# spachausgabe.net
KiCad netlist of a schematic drawn in EAGLE
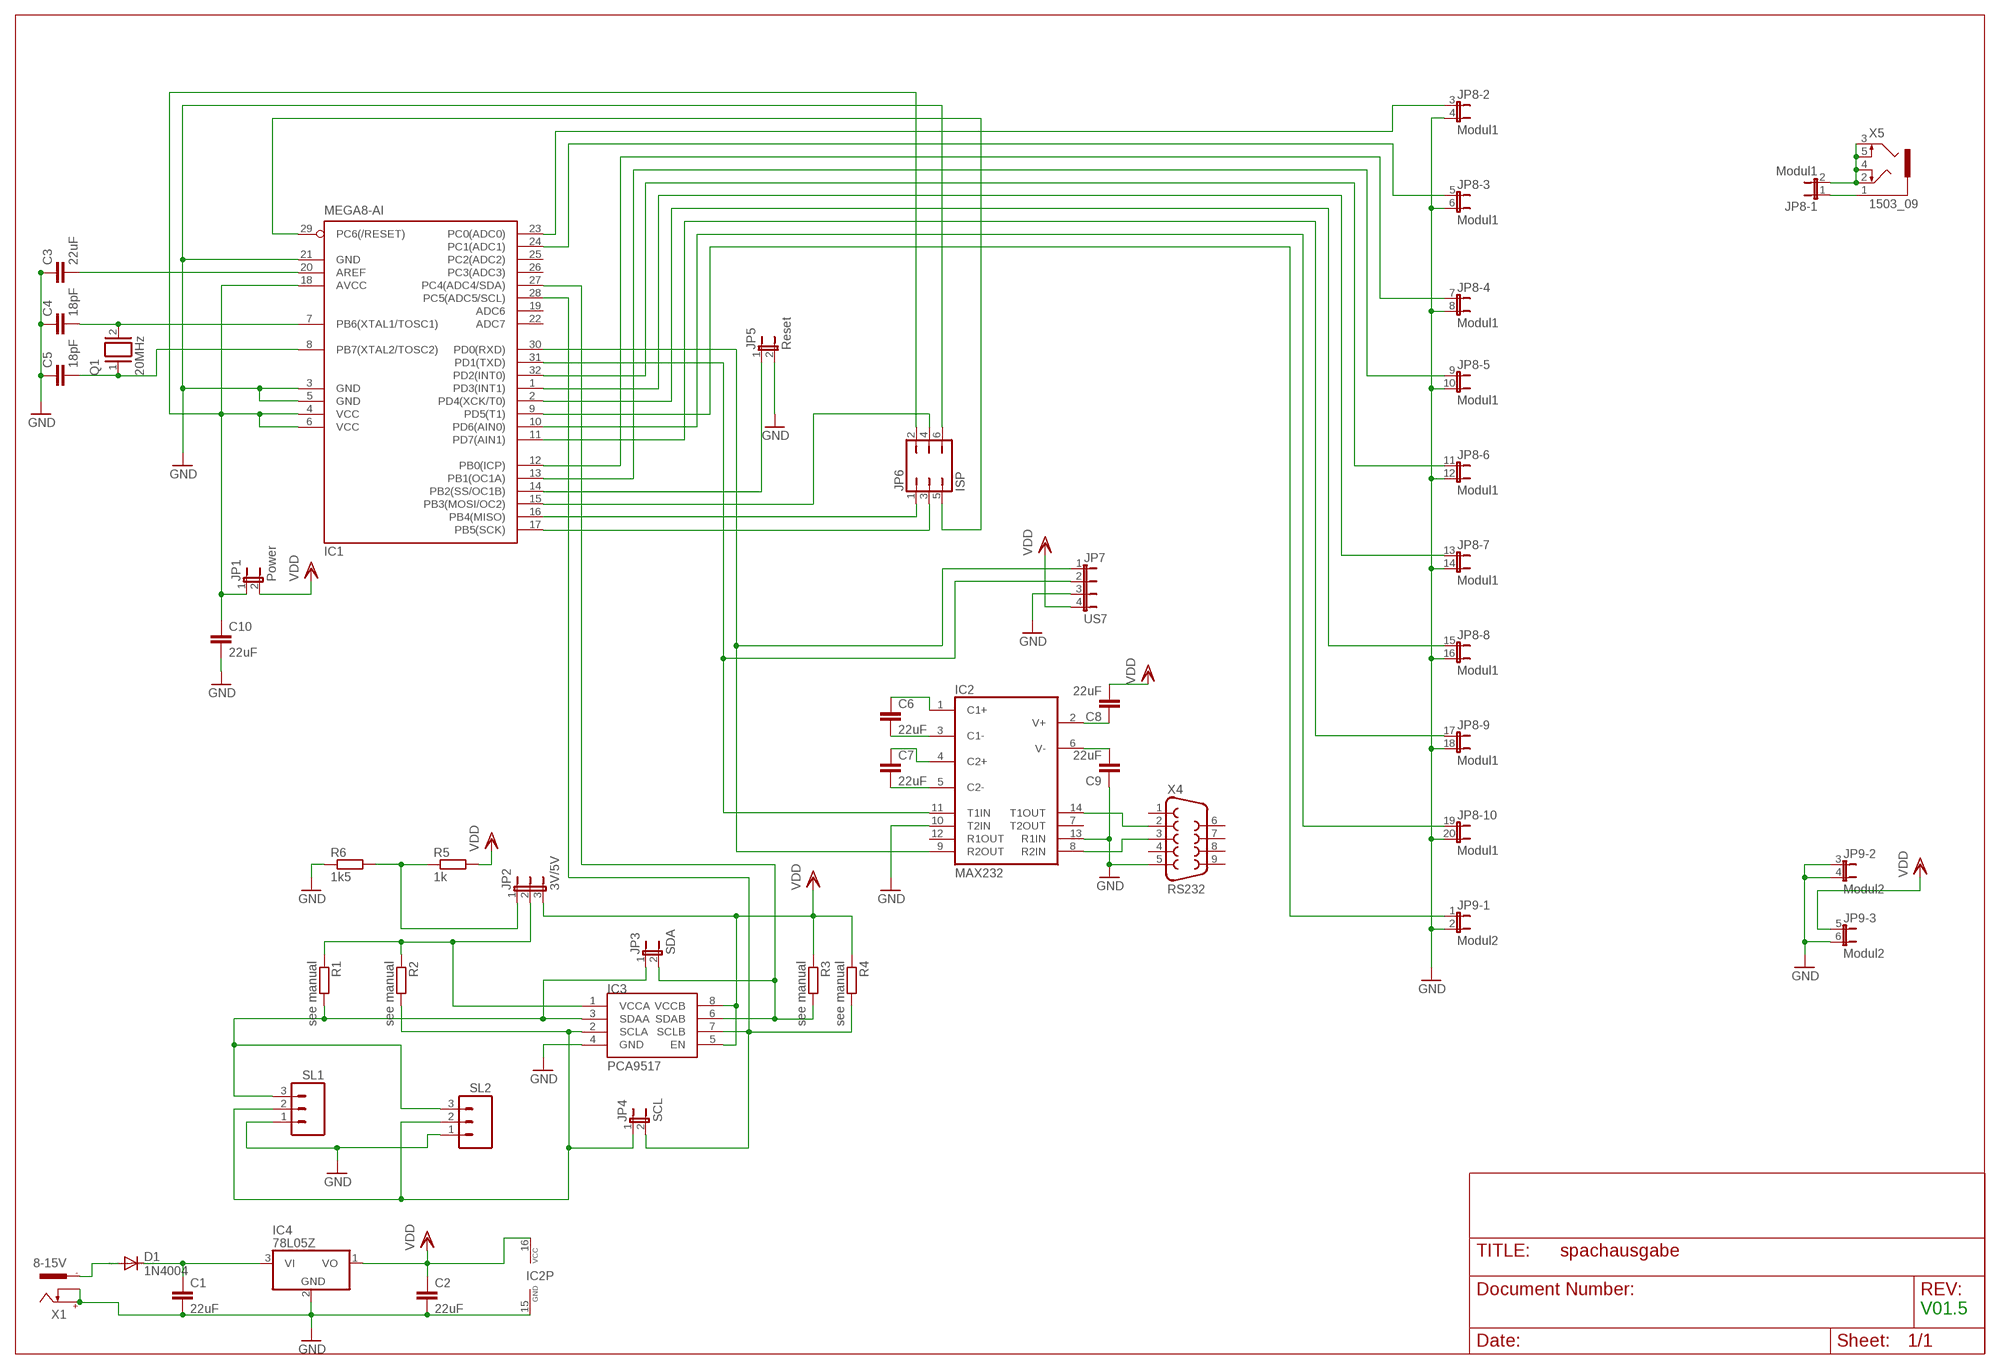
[diagram p0: schematic, sheet 1]

(export (version "E")
  (design (tool "Eeschema 10.0.6"))
  (components
    (comp (ref "C1")
      (value "22uF")
      (footprint "eagle-import:C1206")
      (libsource (lib "eagle-import") (part "C-EUC1206"))
    )
    (comp (ref "C2")
      (value "22uF")
      (footprint "eagle-import:C1206")
      (libsource (lib "eagle-import") (part "C-EUC1206"))
    )
    (comp (ref "C3")
      (value "22uF")
      (footprint "eagle-import:C1206")
      (libsource (lib "eagle-import") (part "C-EUC1206"))
    )
    (comp (ref "C4")
      (value "18pF")
      (footprint "eagle-import:C025-025X050")
      (libsource (lib "eagle-import") (part "resistor_C-EU025-025X050"))
    )
    (comp (ref "C5")
      (value "18pF")
      (footprint "eagle-import:C025-025X050")
      (libsource (lib "eagle-import") (part "resistor_C-EU025-025X050"))
    )
    (comp (ref "C6")
      (value "22uF")
      (footprint "eagle-import:C1206")
      (libsource (lib "eagle-import") (part "C-EUC1206"))
    )
    (comp (ref "C7")
      (value "22uF")
      (footprint "eagle-import:C1206")
      (libsource (lib "eagle-import") (part "C-EUC1206"))
    )
    (comp (ref "C8")
      (value "22uF")
      (footprint "eagle-import:C1206")
      (libsource (lib "eagle-import") (part "C-EUC1206"))
    )
    (comp (ref "C9")
      (value "22uF")
      (footprint "eagle-import:C1206")
      (libsource (lib "eagle-import") (part "C-EUC1206"))
    )
    (comp (ref "C10")
      (value "22uF")
      (footprint "eagle-import:C1206")
      (libsource (lib "eagle-import") (part "C-EUC1206"))
    )
    (comp (ref "D1")
      (value "1N4004")
      (footprint "eagle-import:DO41-10")
      (libsource (lib "eagle-import") (part "1N4004"))
    )
    (comp (ref "IC1")
      (value "MEGA8-AI")
      (footprint "eagle-import:TQFP32-08")
      (fields (field (name "MPN") "ATMEGA8-16AU"))
      (libsource (lib "eagle-import") (part "MEGA8-AI"))
    )
    (comp (ref "IC2")
      (value "MAX232")
      (footprint "eagle-import:DIL16")
      (fields (field (name "MF") "MAXIM") (field (name "MPN") "MAX232ACPE+"))
      (libsource (lib "eagle-import") (part "MAX232"))
    )
    (comp (ref "IC3")
      (value "PCA9517")
      (footprint "eagle-import:SO-08")
      (libsource (lib "eagle-import") (part "PCA9517"))
    )
    (comp (ref "IC4")
      (value "78L05Z")
      (footprint "eagle-import:TO92")
      (libsource (lib "eagle-import") (part "78ZL05"))
    )
    (comp (ref "JP1")
      (value "Power")
      (footprint "eagle-import:JP1")
      (libsource (lib "eagle-import") (part "JP1E"))
    )
    (comp (ref "JP2")
      (value "3V/5V")
      (footprint "eagle-import:JP2")
      (libsource (lib "eagle-import") (part "JP2E"))
    )
    (comp (ref "JP3")
      (value "SDA")
      (footprint "eagle-import:JP1")
      (libsource (lib "eagle-import") (part "JP1E"))
    )
    (comp (ref "JP4")
      (value "SCL")
      (footprint "eagle-import:JP1")
      (libsource (lib "eagle-import") (part "JP1E"))
    )
    (comp (ref "JP5")
      (value "Reset")
      (footprint "eagle-import:JP1")
      (libsource (lib "eagle-import") (part "JP1E"))
    )
    (comp (ref "JP6")
      (value "ISP")
      (footprint "eagle-import:JP3Q")
      (libsource (lib "eagle-import") (part "JP3Q"))
    )
    (comp (ref "JP7")
      (value "US7")
      (footprint "eagle-import:JP4")
      (libsource (lib "eagle-import") (part "JP4E"))
    )
    (comp (ref "JP8")
      (value "Modul1")
      (footprint "eagle-import:JP10Q")
      (libsource (lib "eagle-import") (part "JP10QE"))
    )
    (comp (ref "JP9")
      (value "Modul2")
      (footprint "eagle-import:JP3Q")
      (libsource (lib "eagle-import") (part "JP3QE"))
    )
    (comp (ref "Q1")
      (value "20MHz")
      (footprint "eagle-import:QS")
      (libsource (lib "eagle-import") (part "XTAL/S"))
    )
    (comp (ref "R1")
      (value "see manual")
      (footprint "eagle-import:R1206")
      (libsource (lib "eagle-import") (part "R-EU_R1206"))
    )
    (comp (ref "R2")
      (value "see manual")
      (footprint "eagle-import:M1206")
      (libsource (lib "eagle-import") (part "R-EU_M1206"))
    )
    (comp (ref "R3")
      (value "see manual")
      (footprint "eagle-import:R1206")
      (libsource (lib "eagle-import") (part "R-EU_R1206"))
    )
    (comp (ref "R4")
      (value "see manual")
      (footprint "eagle-import:R1206")
      (libsource (lib "eagle-import") (part "R-EU_R1206"))
    )
    (comp (ref "R5")
      (value "1k")
      (footprint "eagle-import:R1206")
      (libsource (lib "eagle-import") (part "R-EU_R1206"))
    )
    (comp (ref "R6")
      (value "1k5")
      (footprint "eagle-import:R1206")
      (libsource (lib "eagle-import") (part "R-EU_R1206"))
    )
    (comp (ref "SL1")
      (value "M03")
      (footprint "eagle-import:03P")
      (libsource (lib "eagle-import") (part "M03"))
    )
    (comp (ref "SL2")
      (value "M03")
      (footprint "eagle-import:03P")
      (libsource (lib "eagle-import") (part "M03"))
    )
    (comp (ref "X1")
      (value "8-15V")
      (footprint "eagle-import:737992-5")
      (libsource (lib "eagle-import") (part "737992-55"))
    )
    (comp (ref "X4")
      (value "RS232")
      (footprint "eagle-import:F09H")
      (libsource (lib "eagle-import") (part "F09H"))
    )
    (comp (ref "X5")
      (value "1503_09")
      (footprint "eagle-import:1503_09")
      (libsource (lib "eagle-import") (part "1503_09"))
    )
  )
  (nets
    (net (code "1") (name "GND") (class "Default")
      (node (ref "C1") (pin "2") (pinfunction "2_2") (pintype "passive"))
      (node (ref "C10") (pin "2") (pinfunction "2_2") (pintype "passive"))
      (node (ref "C2") (pin "2") (pinfunction "2_2") (pintype "passive"))
      (node (ref "C3") (pin "1") (pinfunction "1_1") (pintype "passive"))
      (node (ref "C4") (pin "1") (pinfunction "1_1") (pintype "passive"))
      (node (ref "C5") (pin "1") (pinfunction "1_1") (pintype "passive"))
      (node (ref "C9") (pin "1") (pinfunction "1_1") (pintype "passive"))
      (node (ref "IC1") (pin "21") (pinfunction "GND_21") (pintype "power_in"))
      (node (ref "IC1") (pin "3") (pinfunction "GND_3") (pintype "power_in"))
      (node (ref "IC1") (pin "5") (pinfunction "GND_5") (pintype "power_in"))
      (node (ref "IC2") (pin "10") (pinfunction "T2IN_10") (pintype "input"))
      (node (ref "IC2") (pin "13") (pinfunction "R1IN_13") (pintype "input"))
      (node (ref "IC2") (pin "15") (pinfunction "GND_15") (pintype "power_in"))
      (node (ref "IC3") (pin "4") (pinfunction "GND_4") (pintype "bidirectional"))
      (node (ref "IC4") (pin "2") (pinfunction "GND_2") (pintype "passive"))
      (node (ref "JP5") (pin "2") (pinfunction "2_2") (pintype "passive"))
      (node (ref "JP6") (pin "6") (pinfunction "6_6") (pintype "passive"))
      (node (ref "JP7") (pin "3") (pinfunction "3_3") (pintype "passive"))
      (node (ref "JP8") (pin "10") (pinfunction "2_10") (pintype "passive"))
      (node (ref "JP8") (pin "12") (pinfunction "2_12") (pintype "passive"))
      (node (ref "JP8") (pin "14") (pinfunction "2_14") (pintype "passive"))
      (node (ref "JP8") (pin "16") (pinfunction "2_16") (pintype "passive"))
      (node (ref "JP8") (pin "18") (pinfunction "2_18") (pintype "passive"))
      (node (ref "JP8") (pin "20") (pinfunction "2_20") (pintype "passive"))
      (node (ref "JP8") (pin "4") (pinfunction "2_4") (pintype "passive"))
      (node (ref "JP8") (pin "6") (pinfunction "2_6") (pintype "passive"))
      (node (ref "JP8") (pin "8") (pinfunction "2_8") (pintype "passive"))
      (node (ref "JP9") (pin "2") (pinfunction "2_2") (pintype "passive"))
      (node (ref "JP9") (pin "3") (pinfunction "1_3") (pintype "passive"))
      (node (ref "JP9") (pin "4") (pinfunction "2_4") (pintype "passive"))
      (node (ref "JP9") (pin "6") (pinfunction "2_6") (pintype "passive"))
      (node (ref "R6") (pin "1") (pinfunction "1_1") (pintype "passive"))
      (node (ref "SL1") (pin "1") (pinfunction "1_1") (pintype "passive"))
      (node (ref "SL2") (pin "1") (pinfunction "1_1") (pintype "passive"))
      (node (ref "X1") (pin "+") (pinfunction "+_+") (pintype "passive"))
      (node (ref "X1") (pin "K") (pinfunction "K_K") (pintype "passive"))
      (node (ref "X4") (pin "5") (pinfunction "5_5") (pintype "passive"))
    )
    (net (code "2") (name "Net-(D1-PadA)") (class "Default")
      (node (ref "D1") (pin "A") (pinfunction "A_A") (pintype "passive"))
      (node (ref "X1") (pin "-1") (pinfunction "-1_-1") (pintype "passive"))
    )
    (net (code "3") (name "Net-(IC1-AREF)") (class "Default")
      (node (ref "C3") (pin "2") (pinfunction "2_2") (pintype "passive"))
      (node (ref "IC1") (pin "20") (pinfunction "AREF_20") (pintype "passive"))
    )
    (net (code "4") (name "Net-(IC1-AVCC)") (class "Default")
      (node (ref "C10") (pin "1") (pinfunction "1_1") (pintype "passive"))
      (node (ref "IC1") (pin "18") (pinfunction "AVCC_18") (pintype "power_in"))
      (node (ref "IC1") (pin "4") (pinfunction "VCC_4") (pintype "power_in"))
      (node (ref "IC1") (pin "6") (pinfunction "VCC_6") (pintype "power_in"))
      (node (ref "JP1") (pin "1") (pinfunction "1_1") (pintype "passive"))
      (node (ref "JP6") (pin "2") (pinfunction "2_2") (pintype "passive"))
    )
    (net (code "5") (name "Net-(IC1-PB0(ICP))") (class "Default")
      (node (ref "IC1") (pin "12") (pinfunction "PB0(ICP)_12") (pintype "bidirectional"))
      (node (ref "JP8") (pin "7") (pinfunction "1_7") (pintype "passive"))
    )
    (net (code "6") (name "Net-(IC1-PB1(OC1A))") (class "Default")
      (node (ref "IC1") (pin "13") (pinfunction "PB1(OC1A)_13") (pintype "bidirectional"))
      (node (ref "JP8") (pin "9") (pinfunction "1_9") (pintype "passive"))
    )
    (net (code "7") (name "Net-(IC1-PB2(SS{slash}OC1B))") (class "Default")
      (node (ref "IC1") (pin "14") (pinfunction "PB2(SS/OC1B)_14") (pintype "bidirectional"))
      (node (ref "JP5") (pin "1") (pinfunction "1_1") (pintype "passive"))
    )
    (net (code "8") (name "Net-(IC1-PB3(MOSI{slash}OC2))") (class "Default")
      (node (ref "IC1") (pin "15") (pinfunction "PB3(MOSI/OC2)_15") (pintype "bidirectional"))
      (node (ref "JP6") (pin "4") (pinfunction "4_4") (pintype "passive"))
    )
    (net (code "9") (name "Net-(IC1-PB4(MISO))") (class "Default")
      (node (ref "IC1") (pin "16") (pinfunction "PB4(MISO)_16") (pintype "bidirectional"))
      (node (ref "JP6") (pin "1") (pinfunction "1_1") (pintype "passive"))
    )
    (net (code "10") (name "Net-(IC1-PB5(SCK))") (class "Default")
      (node (ref "IC1") (pin "17") (pinfunction "PB5(SCK)_17") (pintype "bidirectional"))
      (node (ref "JP6") (pin "3") (pinfunction "3_3") (pintype "passive"))
    )
    (net (code "11") (name "Net-(IC1-PB6(XTAL1{slash}TOSC1))") (class "Default")
      (node (ref "C4") (pin "2") (pinfunction "2_2") (pintype "passive"))
      (node (ref "IC1") (pin "7") (pinfunction "PB6(XTAL1/TOSC1)_7") (pintype "bidirectional"))
      (node (ref "Q1") (pin "2") (pinfunction "2_2") (pintype "passive"))
    )
    (net (code "12") (name "Net-(IC1-PB7(XTAL2{slash}TOSC2))") (class "Default")
      (node (ref "C5") (pin "2") (pinfunction "2_2") (pintype "passive"))
      (node (ref "IC1") (pin "8") (pinfunction "PB7(XTAL2/TOSC2)_8") (pintype "bidirectional"))
      (node (ref "Q1") (pin "1") (pinfunction "1_1") (pintype "passive"))
    )
    (net (code "13") (name "Net-(IC1-PC0(ADC0))") (class "Default")
      (node (ref "IC1") (pin "23") (pinfunction "PC0(ADC0)_23") (pintype "bidirectional"))
      (node (ref "JP8") (pin "3") (pinfunction "1_3") (pintype "passive"))
    )
    (net (code "14") (name "Net-(IC1-PC1(ADC1))") (class "Default")
      (node (ref "IC1") (pin "24") (pinfunction "PC1(ADC1)_24") (pintype "bidirectional"))
      (node (ref "JP8") (pin "5") (pinfunction "1_5") (pintype "passive"))
    )
    (net (code "15") (name "Net-(IC1-PC4(ADC4{slash}SDA))") (class "Default")
      (node (ref "IC1") (pin "27") (pinfunction "PC4(ADC4/SDA)_27") (pintype "bidirectional"))
      (node (ref "IC3") (pin "6") (pinfunction "SDAB_6") (pintype "bidirectional"))
      (node (ref "JP3") (pin "2") (pinfunction "2_2") (pintype "passive"))
      (node (ref "R3") (pin "2") (pinfunction "2_2") (pintype "passive"))
    )
    (net (code "16") (name "Net-(IC1-PC5(ADC5{slash}SCL))") (class "Default")
      (node (ref "IC1") (pin "28") (pinfunction "PC5(ADC5/SCL)_28") (pintype "bidirectional"))
      (node (ref "IC3") (pin "7") (pinfunction "SCLB_7") (pintype "bidirectional"))
      (node (ref "JP4") (pin "2") (pinfunction "2_2") (pintype "passive"))
      (node (ref "R4") (pin "2") (pinfunction "2_2") (pintype "passive"))
    )
    (net (code "17") (name "Net-(IC1-PC6({slash}RESET))") (class "Default")
      (node (ref "IC1") (pin "29") (pinfunction "PC6(/RESET)_29") (pintype "bidirectional"))
      (node (ref "JP6") (pin "5") (pinfunction "5_5") (pintype "passive"))
    )
    (net (code "18") (name "Net-(IC1-PD0(RXD))") (class "Default")
      (node (ref "IC1") (pin "30") (pinfunction "PD0(RXD)_30") (pintype "bidirectional"))
      (node (ref "IC2") (pin "9") (pinfunction "R2OUT_9") (pintype "output"))
      (node (ref "JP7") (pin "1") (pinfunction "1_1") (pintype "passive"))
    )
    (net (code "19") (name "Net-(IC1-PD1(TXD))") (class "Default")
      (node (ref "IC1") (pin "31") (pinfunction "PD1(TXD)_31") (pintype "bidirectional"))
      (node (ref "IC2") (pin "11") (pinfunction "T1IN_11") (pintype "input"))
      (node (ref "JP7") (pin "2") (pinfunction "2_2") (pintype "passive"))
    )
    (net (code "20") (name "Net-(IC1-PD2(INT0))") (class "Default")
      (node (ref "IC1") (pin "32") (pinfunction "PD2(INT0)_32") (pintype "bidirectional"))
      (node (ref "JP8") (pin "11") (pinfunction "1_11") (pintype "passive"))
    )
    (net (code "21") (name "Net-(IC1-PD3(INT1))") (class "Default")
      (node (ref "IC1") (pin "1") (pinfunction "PD3(INT1)_1") (pintype "bidirectional"))
      (node (ref "JP8") (pin "13") (pinfunction "1_13") (pintype "passive"))
    )
    (net (code "22") (name "Net-(IC1-PD4(XCK{slash}T0))") (class "Default")
      (node (ref "IC1") (pin "2") (pinfunction "PD4(XCK/T0)_2") (pintype "bidirectional"))
      (node (ref "JP8") (pin "15") (pinfunction "1_15") (pintype "passive"))
    )
    (net (code "23") (name "Net-(IC1-PD5(T1))") (class "Default")
      (node (ref "IC1") (pin "9") (pinfunction "PD5(T1)_9") (pintype "bidirectional"))
      (node (ref "JP9") (pin "1") (pinfunction "1_1") (pintype "passive"))
    )
    (net (code "24") (name "Net-(IC1-PD6(AIN0))") (class "Default")
      (node (ref "IC1") (pin "10") (pinfunction "PD6(AIN0)_10") (pintype "bidirectional"))
      (node (ref "JP8") (pin "19") (pinfunction "1_19") (pintype "passive"))
    )
    (net (code "25") (name "Net-(IC1-PD7(AIN1))") (class "Default")
      (node (ref "IC1") (pin "11") (pinfunction "PD7(AIN1)_11") (pintype "bidirectional"))
      (node (ref "JP8") (pin "17") (pinfunction "1_17") (pintype "passive"))
    )
    (net (code "26") (name "Net-(IC2A-C1+)") (class "Default")
      (node (ref "C6") (pin "1") (pinfunction "1_1") (pintype "passive"))
      (node (ref "IC2") (pin "1") (pinfunction "C1+_1") (pintype "bidirectional"))
    )
    (net (code "27") (name "Net-(IC2A-C1-)") (class "Default")
      (node (ref "C6") (pin "2") (pinfunction "2_2") (pintype "passive"))
      (node (ref "IC2") (pin "3") (pinfunction "C1-_3") (pintype "bidirectional"))
    )
    (net (code "28") (name "Net-(IC2A-C2+)") (class "Default")
      (node (ref "C7") (pin "1") (pinfunction "1_1") (pintype "passive"))
      (node (ref "IC2") (pin "4") (pinfunction "C2+_4") (pintype "bidirectional"))
    )
    (net (code "29") (name "Net-(IC2A-C2-)") (class "Default")
      (node (ref "C7") (pin "2") (pinfunction "2_2") (pintype "passive"))
      (node (ref "IC2") (pin "5") (pinfunction "C2-_5") (pintype "bidirectional"))
    )
    (net (code "30") (name "Net-(IC2A-R2IN)") (class "Default")
      (node (ref "IC2") (pin "8") (pinfunction "R2IN_8") (pintype "input"))
      (node (ref "X4") (pin "3") (pinfunction "3_3") (pintype "passive"))
    )
    (net (code "31") (name "Net-(IC2A-T1OUT)") (class "Default")
      (node (ref "IC2") (pin "14") (pinfunction "T1OUT_14") (pintype "output"))
      (node (ref "X4") (pin "2") (pinfunction "2_2") (pintype "passive"))
    )
    (net (code "32") (name "Net-(IC2A-V+)") (class "Default")
      (node (ref "C8") (pin "1") (pinfunction "1_1") (pintype "passive"))
      (node (ref "IC2") (pin "2") (pinfunction "V+_2") (pintype "bidirectional"))
    )
    (net (code "33") (name "Net-(IC2A-V-)") (class "Default")
      (node (ref "C9") (pin "2") (pinfunction "2_2") (pintype "passive"))
      (node (ref "IC2") (pin "6") (pinfunction "V-_6") (pintype "bidirectional"))
    )
    (net (code "34") (name "Net-(IC3-SCLA)") (class "Default")
      (node (ref "IC3") (pin "2") (pinfunction "SCLA_2") (pintype "bidirectional"))
      (node (ref "JP4") (pin "1") (pinfunction "1_1") (pintype "passive"))
      (node (ref "R2") (pin "2") (pinfunction "2_2") (pintype "passive"))
      (node (ref "SL1") (pin "2") (pinfunction "2_2") (pintype "passive"))
      (node (ref "SL2") (pin "2") (pinfunction "2_2") (pintype "passive"))
    )
    (net (code "35") (name "Net-(IC3-SDAA)") (class "Default")
      (node (ref "IC3") (pin "3") (pinfunction "SDAA_3") (pintype "bidirectional"))
      (node (ref "JP3") (pin "1") (pinfunction "1_1") (pintype "passive"))
      (node (ref "R1") (pin "2") (pinfunction "2_2") (pintype "passive"))
      (node (ref "SL1") (pin "3") (pinfunction "3_3") (pintype "passive"))
      (node (ref "SL2") (pin "3") (pinfunction "3_3") (pintype "passive"))
    )
    (net (code "36") (name "Net-(IC3-VCCA)") (class "Default")
      (node (ref "IC3") (pin "1") (pinfunction "VCCA_1") (pintype "bidirectional"))
      (node (ref "JP2") (pin "2") (pinfunction "2_2") (pintype "passive"))
      (node (ref "R1") (pin "1") (pinfunction "1_1") (pintype "passive"))
      (node (ref "R2") (pin "1") (pinfunction "1_1") (pintype "passive"))
    )
    (net (code "37") (name "Net-(IC4-VI)") (class "Default")
      (node (ref "C1") (pin "1") (pinfunction "1_1") (pintype "passive"))
      (node (ref "D1") (pin "C") (pinfunction "C_C") (pintype "passive"))
      (node (ref "IC4") (pin "3") (pinfunction "VI_3") (pintype "input"))
    )
    (net (code "38") (name "Net-(JP2-Pad1)") (class "Default")
      (node (ref "JP2") (pin "1") (pinfunction "1_1") (pintype "passive"))
      (node (ref "R5") (pin "1") (pinfunction "1_1") (pintype "passive"))
      (node (ref "R6") (pin "2") (pinfunction "2_2") (pintype "passive"))
    )
    (net (code "39") (name "Net-(JP8-Pad1)") (class "Default")
      (node (ref "JP8") (pin "1") (pinfunction "1_1") (pintype "passive"))
      (node (ref "X5") (pin "1") (pinfunction "1_1") (pintype "passive"))
    )
    (net (code "40") (name "Net-(JP8-Pad2)") (class "Default")
      (node (ref "JP8") (pin "2") (pinfunction "2_2") (pintype "passive"))
      (node (ref "X5") (pin "2") (pinfunction "2_2") (pintype "passive"))
      (node (ref "X5") (pin "3") (pinfunction "3_3") (pintype "passive"))
      (node (ref "X5") (pin "4") (pinfunction "4_4") (pintype "passive"))
      (node (ref "X5") (pin "5") (pinfunction "5_5") (pintype "passive"))
    )
    (net (code "41") (name "VDD") (class "Default")
      (node (ref "C2") (pin "1") (pinfunction "1_1") (pintype "passive"))
      (node (ref "C8") (pin "2") (pinfunction "2_2") (pintype "passive"))
      (node (ref "IC2") (pin "16") (pinfunction "VCC_16") (pintype "power_in"))
      (node (ref "IC3") (pin "5") (pinfunction "EN_5") (pintype "bidirectional"))
      (node (ref "IC3") (pin "8") (pinfunction "VCCB_8") (pintype "bidirectional"))
      (node (ref "IC4") (pin "1") (pinfunction "VO_1") (pintype "passive"))
      (node (ref "JP1") (pin "2") (pinfunction "2_2") (pintype "passive"))
      (node (ref "JP2") (pin "3") (pinfunction "3_3") (pintype "passive"))
      (node (ref "JP7") (pin "4") (pinfunction "4_4") (pintype "passive"))
      (node (ref "JP9") (pin "5") (pinfunction "1_5") (pintype "passive"))
      (node (ref "R3") (pin "1") (pinfunction "1_1") (pintype "passive"))
      (node (ref "R4") (pin "1") (pinfunction "1_1") (pintype "passive"))
      (node (ref "R5") (pin "2") (pinfunction "2_2") (pintype "passive"))
    )
    (net (code "42") (name "unconnected-(IC1-ADC6-Pad19)") (class "Default")
      (node (ref "IC1") (pin "19") (pinfunction "ADC6_19") (pintype "bidirectional"))
    )
    (net (code "43") (name "unconnected-(IC1-ADC7-Pad22)") (class "Default")
      (node (ref "IC1") (pin "22") (pinfunction "ADC7_22") (pintype "bidirectional"))
    )
    (net (code "44") (name "unconnected-(IC1-PC2(ADC2)-Pad25)") (class "Default")
      (node (ref "IC1") (pin "25") (pinfunction "PC2(ADC2)_25") (pintype "bidirectional"))
    )
    (net (code "45") (name "unconnected-(IC1-PC3(ADC3)-Pad26)") (class "Default")
      (node (ref "IC1") (pin "26") (pinfunction "PC3(ADC3)_26") (pintype "bidirectional"))
    )
    (net (code "46") (name "unconnected-(IC2A-R1OUT-Pad12)") (class "Default")
      (node (ref "IC2") (pin "12") (pinfunction "R1OUT_12") (pintype "output"))
    )
    (net (code "47") (name "unconnected-(IC2A-T2OUT-Pad7)") (class "Default")
      (node (ref "IC2") (pin "7") (pinfunction "T2OUT_7") (pintype "output"))
    )
    (net (code "48") (name "unconnected-(X1-Pad-2)") (class "Default")
      (node (ref "X1") (pin "-2") (pinfunction "-2_-2") (pintype "passive"))
    )
    (net (code "49") (name "unconnected-(X4-Pad1)") (class "Default")
      (node (ref "X4") (pin "1") (pinfunction "1_1") (pintype "passive"))
    )
    (net (code "50") (name "unconnected-(X4-Pad4)") (class "Default")
      (node (ref "X4") (pin "4") (pinfunction "4_4") (pintype "passive"))
    )
    (net (code "51") (name "unconnected-(X4-Pad6)") (class "Default")
      (node (ref "X4") (pin "6") (pinfunction "6_6") (pintype "passive"))
    )
    (net (code "52") (name "unconnected-(X4-Pad7)") (class "Default")
      (node (ref "X4") (pin "7") (pinfunction "7_7") (pintype "passive"))
    )
    (net (code "53") (name "unconnected-(X4-Pad8)") (class "Default")
      (node (ref "X4") (pin "8") (pinfunction "8_8") (pintype "passive"))
    )
    (net (code "54") (name "unconnected-(X4-Pad9)") (class "Default")
      (node (ref "X4") (pin "9") (pinfunction "9_9") (pintype "passive"))
    )
  )
)
